# Power_switch_robot_kecil.net
KiCad netlist of a schematic drawn in EAGLE
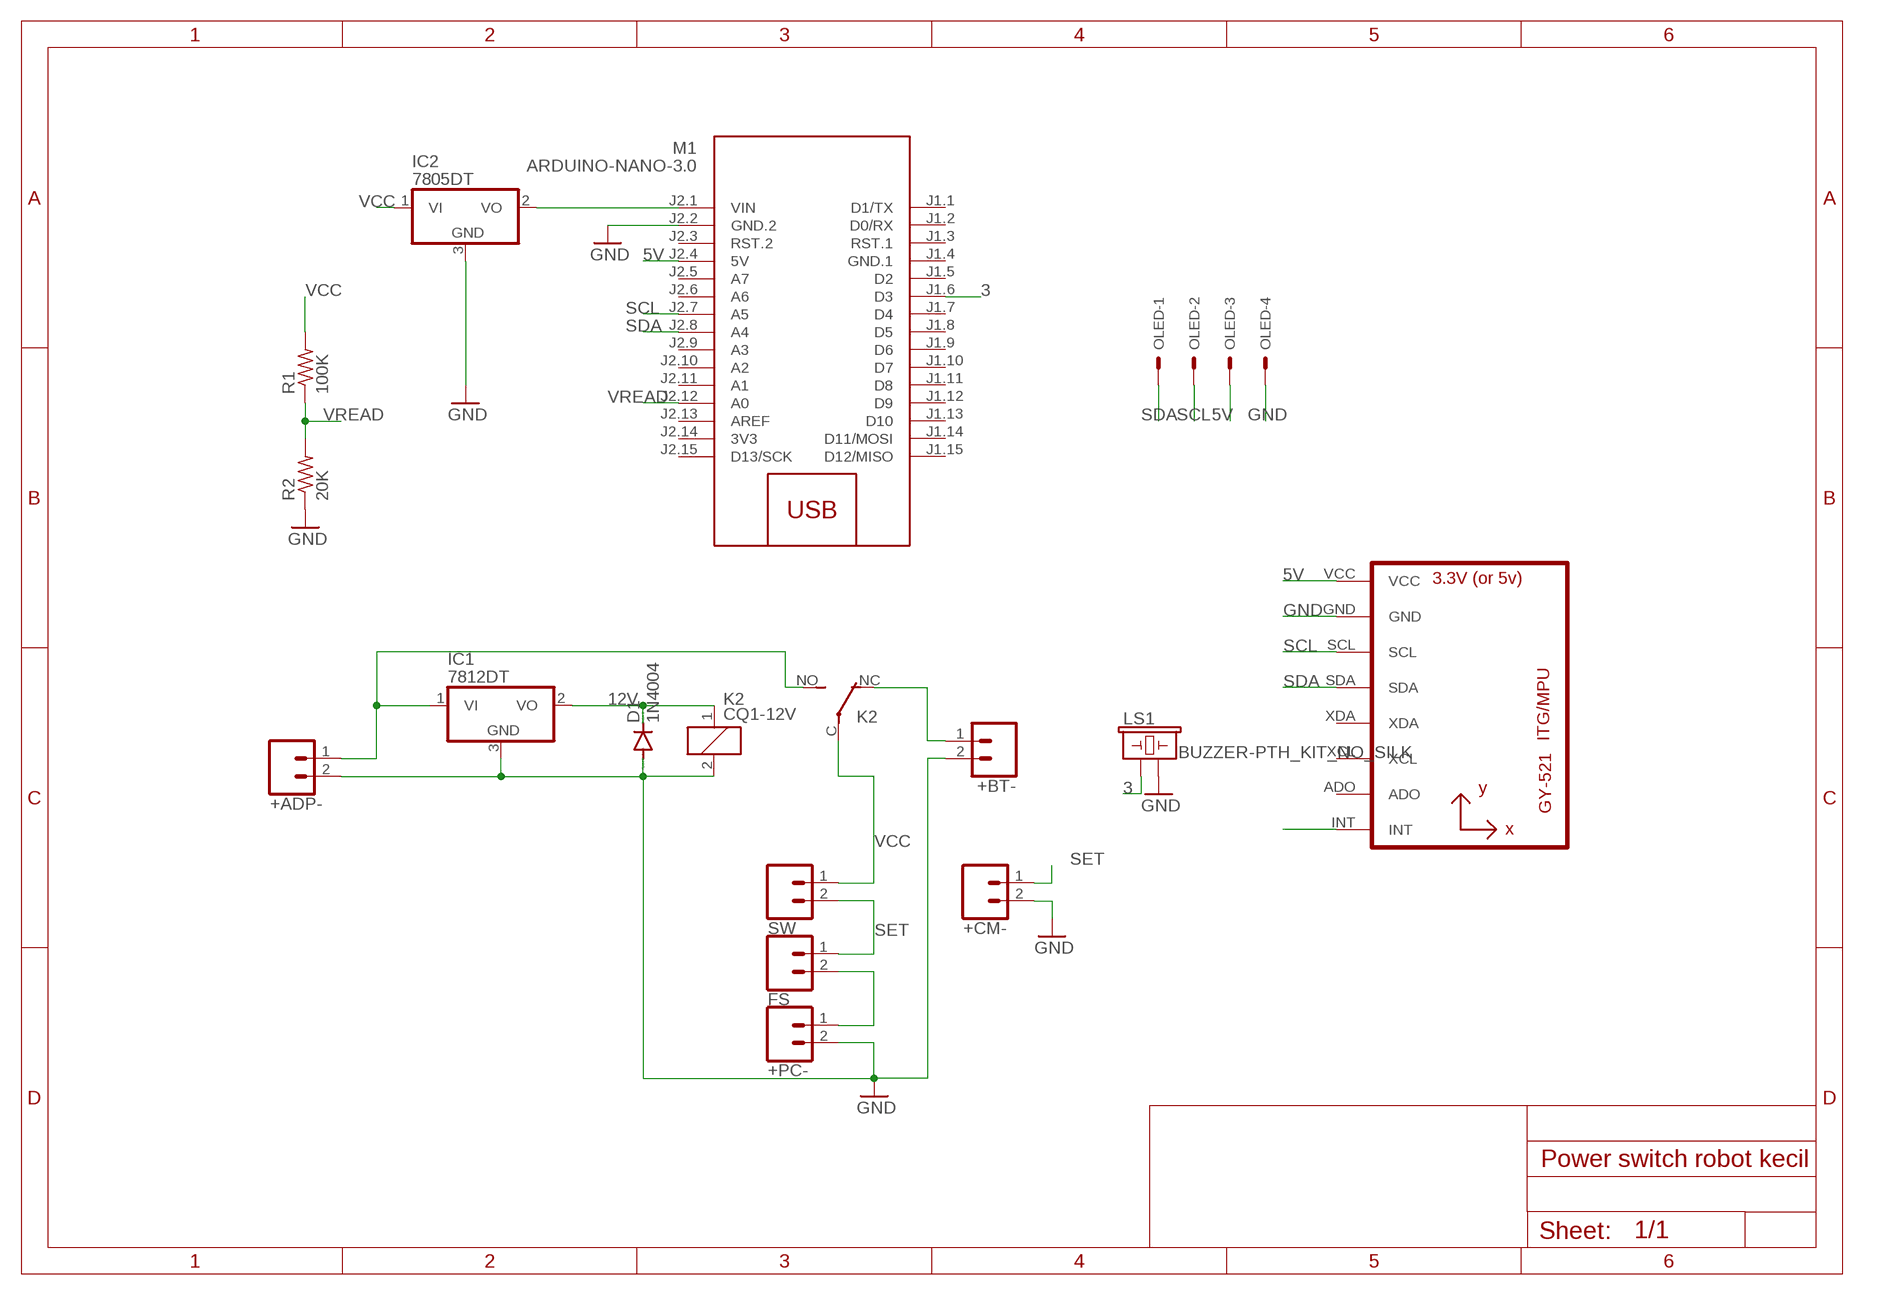
[diagram p0: schematic, sheet 1]

(export (version "E")
  (design (tool "Eeschema 10.0.6"))
  (components
    (comp (ref "+ADP-")
      (value "CONN_02PTH4")
      (footprint "eagle-import:1X02_XTRA_BIG")
      (libsource (lib "eagle-import") (part "CONN_02PTH4"))
    )
    (comp (ref "+BT-")
      (value "CONN_02PTH4")
      (footprint "eagle-import:1X02_XTRA_BIG")
      (libsource (lib "eagle-import") (part "CONN_02PTH4"))
    )
    (comp (ref "+CM-")
      (value "CONN_02PTH4")
      (footprint "eagle-import:1X02_XTRA_BIG")
      (libsource (lib "eagle-import") (part "CONN_02PTH4"))
    )
    (comp (ref "+PC-")
      (value "CONN_02PTH4")
      (footprint "eagle-import:1X02_XTRA_BIG")
      (libsource (lib "eagle-import") (part "CONN_02PTH4"))
    )
    (comp (ref "D1")
      (value "1N4004")
      (footprint "eagle-import:DO41-10")
      (libsource (lib "eagle-import") (part "1N4004"))
    )
    (comp (ref "FS")
      (value "CONN_02PTH4")
      (footprint "eagle-import:1X02_XTRA_BIG")
      (libsource (lib "eagle-import") (part "CONN_02PTH4"))
    )
    (comp (ref "IC1")
      (value "7812DT")
      (footprint "eagle-import:TO252")
      (libsource (lib "eagle-import") (part "78DT12"))
    )
    (comp (ref "IC2")
      (value "7805DT")
      (footprint "eagle-import:TO252")
      (libsource (lib "eagle-import") (part "78DT05"))
    )
    (comp (ref "K2")
      (value "CQ1-12V")
      (footprint "eagle-import:CQ1")
      (libsource (lib "eagle-import") (part "CQ1-12V"))
    )
    (comp (ref "LS1")
      (value "BUZZER-PTH_KIT_NO_SILK")
      (footprint "eagle-import:BUZZER-12MM-NS-KIT")
      (libsource (lib "eagle-import") (part "BUZZER-PTH_KIT_NO_SILK"))
    )
    (comp (ref "M1")
      (value "ARDUINO-NANO-3.0")
      (footprint "eagle-import:ARDUINO-NANO-3.0")
      (libsource (lib "eagle-import") (part "ARDUINO-NANO-3.0"))
    )
    (comp (ref "OLED")
      (value "22-27-2041-04")
      (footprint "eagle-import:6410-04")
      (fields (field (name "MF") "MOLEX"))
      (libsource (lib "eagle-import") (part "22-?-0427-2041"))
    )
    (comp (ref "R1")
      (value "100K")
      (footprint "eagle-import:0207_10")
      (libsource (lib "eagle-import") (part "R-US_0207/10"))
    )
    (comp (ref "R2")
      (value "20K")
      (footprint "eagle-import:0207_10")
      (libsource (lib "eagle-import") (part "R-US_0207/10"))
    )
    (comp (ref "SW")
      (value "CONN_02PTH4")
      (footprint "eagle-import:1X02_XTRA_BIG")
      (libsource (lib "eagle-import") (part "CONN_02PTH4"))
    )
    (comp (ref "U1")
      (value "GY-521MPU6050")
      (footprint "eagle-import:GY-521")
      (libsource (lib "eagle-import") (part "GY-521MPU6050"))
    )
  )
  (nets
    (net (code "1") (name "/3") (class "Default")
      (node (ref "LS1") (pin "+") (pinfunction "1_+") (pintype "passive"))
      (node (ref "M1") (pin "J1.6") (pinfunction "D3_J1.6") (pintype "bidirectional"))
    )
    (net (code "2") (name "/3V3") (class "Default")
      (node (ref "M1") (pin "J2.14") (pinfunction "3V3_J2.14") (pintype "power_in"))
    )
    (net (code "3") (name "/5V") (class "Default")
      (node (ref "M1") (pin "J2.4") (pinfunction "5V_J2.4") (pintype "power_in"))
      (node (ref "OLED") (pin "3") (pinfunction "S_3") (pintype "passive"))
      (node (ref "U1") (pin "VCC") (pinfunction "VCC_VCC") (pintype "bidirectional"))
    )
    (net (code "4") (name "/12V") (class "Default")
      (node (ref "D1") (pin "C") (pinfunction "C_C") (pintype "passive"))
      (node (ref "IC1") (pin "2") (pinfunction "VO_2") (pintype "passive"))
      (node (ref "K2") (pin "1") (pinfunction "1_1") (pintype "passive"))
    )
    (net (code "5") (name "/GND.1") (class "Default")
      (node (ref "M1") (pin "J1.4") (pinfunction "GND.1_J1.4") (pintype "power_in"))
    )
    (net (code "6") (name "/SCL") (class "Default")
      (node (ref "M1") (pin "J2.7") (pinfunction "A5_J2.7") (pintype "bidirectional"))
      (node (ref "OLED") (pin "2") (pinfunction "S_2") (pintype "passive"))
      (node (ref "U1") (pin "SCL") (pinfunction "SCL_SCL") (pintype "bidirectional"))
    )
    (net (code "7") (name "/SDA") (class "Default")
      (node (ref "M1") (pin "J2.8") (pinfunction "A4_J2.8") (pintype "bidirectional"))
      (node (ref "OLED") (pin "1") (pinfunction "S_1") (pintype "passive"))
      (node (ref "U1") (pin "SDA") (pinfunction "SDA_SDA") (pintype "bidirectional"))
    )
    (net (code "8") (name "/SET") (class "Default")
      (node (ref "+CM-") (pin "1") (pinfunction "1_1") (pintype "passive"))
      (node (ref "FS") (pin "1") (pinfunction "1_1") (pintype "passive"))
      (node (ref "SW") (pin "2") (pinfunction "2_2") (pintype "passive"))
    )
    (net (code "9") (name "/VCC") (class "Default")
      (node (ref "IC2") (pin "1") (pinfunction "VI_1") (pintype "input"))
      (node (ref "K2") (pin "C") (pinfunction "P_C") (pintype "passive"))
      (node (ref "R1") (pin "2") (pinfunction "2_2") (pintype "passive"))
      (node (ref "SW") (pin "1") (pinfunction "1_1") (pintype "passive"))
    )
    (net (code "10") (name "/VREAD") (class "Default")
      (node (ref "M1") (pin "J2.12") (pinfunction "A0_J2.12") (pintype "bidirectional"))
      (node (ref "R1") (pin "1") (pinfunction "1_1") (pintype "passive"))
      (node (ref "R2") (pin "2") (pinfunction "2_2") (pintype "passive"))
    )
    (net (code "11") (name "GND") (class "Default")
      (node (ref "+ADP-") (pin "2") (pinfunction "2_2") (pintype "passive"))
      (node (ref "+BT-") (pin "2") (pinfunction "2_2") (pintype "passive"))
      (node (ref "+CM-") (pin "2") (pinfunction "2_2") (pintype "passive"))
      (node (ref "+PC-") (pin "2") (pinfunction "2_2") (pintype "passive"))
      (node (ref "D1") (pin "A") (pinfunction "A_A") (pintype "passive"))
      (node (ref "IC1") (pin "3") (pinfunction "GND_3") (pintype "passive"))
      (node (ref "IC2") (pin "3") (pinfunction "GND_3") (pintype "passive"))
      (node (ref "K2") (pin "2") (pinfunction "2_2") (pintype "passive"))
      (node (ref "LS1") (pin "-") (pinfunction "2_-") (pintype "passive"))
      (node (ref "M1") (pin "J2.2") (pinfunction "GND.2_J2.2") (pintype "power_in"))
      (node (ref "OLED") (pin "4") (pinfunction "S_4") (pintype "passive"))
      (node (ref "R2") (pin "1") (pinfunction "1_1") (pintype "passive"))
      (node (ref "U1") (pin "GND") (pinfunction "GND_GND") (pintype "bidirectional"))
    )
    (net (code "12") (name "Net-(+PC--Pad1)") (class "Default")
      (node (ref "+PC-") (pin "1") (pinfunction "1_1") (pintype "passive"))
      (node (ref "FS") (pin "2") (pinfunction "2_2") (pintype "passive"))
    )
    (net (code "13") (name "Net-(IC1-VI)") (class "Default")
      (node (ref "+ADP-") (pin "1") (pinfunction "1_1") (pintype "passive"))
      (node (ref "IC1") (pin "1") (pinfunction "VI_1") (pintype "input"))
      (node (ref "K2") (pin "NO") (pinfunction "S_NO") (pintype "passive"))
    )
    (net (code "14") (name "Net-(IC2-VO)") (class "Default")
      (node (ref "IC2") (pin "2") (pinfunction "VO_2") (pintype "passive"))
      (node (ref "M1") (pin "J2.1") (pinfunction "VIN_J2.1") (pintype "power_in"))
    )
    (net (code "15") (name "Net-(K2B-O)") (class "Default")
      (node (ref "+BT-") (pin "1") (pinfunction "1_1") (pintype "passive"))
      (node (ref "K2") (pin "NC") (pinfunction "O_NC") (pintype "passive"))
    )
    (net (code "16") (name "unconnected-(M1-A1-PadJ2.11)") (class "Default")
      (node (ref "M1") (pin "J2.11") (pinfunction "A1_J2.11") (pintype "bidirectional"))
    )
    (net (code "17") (name "unconnected-(M1-A2-PadJ2.10)") (class "Default")
      (node (ref "M1") (pin "J2.10") (pinfunction "A2_J2.10") (pintype "bidirectional"))
    )
    (net (code "18") (name "unconnected-(M1-A3-PadJ2.9)") (class "Default")
      (node (ref "M1") (pin "J2.9") (pinfunction "A3_J2.9") (pintype "bidirectional"))
    )
    (net (code "19") (name "unconnected-(M1-A6-PadJ2.6)") (class "Default")
      (node (ref "M1") (pin "J2.6") (pinfunction "A6_J2.6") (pintype "bidirectional"))
    )
    (net (code "20") (name "unconnected-(M1-A7-PadJ2.5)") (class "Default")
      (node (ref "M1") (pin "J2.5") (pinfunction "A7_J2.5") (pintype "bidirectional"))
    )
    (net (code "21") (name "unconnected-(M1-AREF-PadJ2.13)") (class "Default")
      (node (ref "M1") (pin "J2.13") (pinfunction "AREF_J2.13") (pintype "bidirectional"))
    )
    (net (code "22") (name "unconnected-(M1-D0{slash}RX-PadJ1.2)") (class "Default")
      (node (ref "M1") (pin "J1.2") (pinfunction "D0/RX_J1.2") (pintype "bidirectional"))
    )
    (net (code "23") (name "unconnected-(M1-D1{slash}TX-PadJ1.1)") (class "Default")
      (node (ref "M1") (pin "J1.1") (pinfunction "D1/TX_J1.1") (pintype "bidirectional"))
    )
    (net (code "24") (name "unconnected-(M1-D2-PadJ1.5)") (class "Default")
      (node (ref "M1") (pin "J1.5") (pinfunction "D2_J1.5") (pintype "bidirectional"))
    )
    (net (code "25") (name "unconnected-(M1-D4-PadJ1.7)") (class "Default")
      (node (ref "M1") (pin "J1.7") (pinfunction "D4_J1.7") (pintype "bidirectional"))
    )
    (net (code "26") (name "unconnected-(M1-D5-PadJ1.8)") (class "Default")
      (node (ref "M1") (pin "J1.8") (pinfunction "D5_J1.8") (pintype "bidirectional"))
    )
    (net (code "27") (name "unconnected-(M1-D6-PadJ1.9)") (class "Default")
      (node (ref "M1") (pin "J1.9") (pinfunction "D6_J1.9") (pintype "bidirectional"))
    )
    (net (code "28") (name "unconnected-(M1-D7-PadJ1.10)") (class "Default")
      (node (ref "M1") (pin "J1.10") (pinfunction "D7_J1.10") (pintype "bidirectional"))
    )
    (net (code "29") (name "unconnected-(M1-D8-PadJ1.11)") (class "Default")
      (node (ref "M1") (pin "J1.11") (pinfunction "D8_J1.11") (pintype "bidirectional"))
    )
    (net (code "30") (name "unconnected-(M1-D9-PadJ1.12)") (class "Default")
      (node (ref "M1") (pin "J1.12") (pinfunction "D9_J1.12") (pintype "bidirectional"))
    )
    (net (code "31") (name "unconnected-(M1-D10-PadJ1.13)") (class "Default")
      (node (ref "M1") (pin "J1.13") (pinfunction "D10_J1.13") (pintype "bidirectional"))
    )
    (net (code "32") (name "unconnected-(M1-D11{slash}MOSI-PadJ1.14)") (class "Default")
      (node (ref "M1") (pin "J1.14") (pinfunction "D11/MOSI_J1.14") (pintype "bidirectional"))
    )
    (net (code "33") (name "unconnected-(M1-D12{slash}MISO-PadJ1.15)") (class "Default")
      (node (ref "M1") (pin "J1.15") (pinfunction "D12/MISO_J1.15") (pintype "bidirectional"))
    )
    (net (code "34") (name "unconnected-(M1-D13{slash}SCK-PadJ2.15)") (class "Default")
      (node (ref "M1") (pin "J2.15") (pinfunction "D13/SCK_J2.15") (pintype "bidirectional"))
    )
    (net (code "35") (name "unconnected-(M1-RST.1-PadJ1.3)") (class "Default")
      (node (ref "M1") (pin "J1.3") (pinfunction "RST.1_J1.3") (pintype "bidirectional"))
    )
    (net (code "36") (name "unconnected-(M1-RST.2-PadJ2.3)") (class "Default")
      (node (ref "M1") (pin "J2.3") (pinfunction "RST.2_J2.3") (pintype "bidirectional"))
    )
    (net (code "37") (name "unconnected-(U1-PadADO)") (class "Default")
      (node (ref "U1") (pin "ADO") (pinfunction "ADO_ADO") (pintype "bidirectional"))
    )
    (net (code "38") (name "unconnected-(U1-PadINT)") (class "Default")
      (node (ref "U1") (pin "INT") (pinfunction "INT_INT") (pintype "bidirectional"))
    )
    (net (code "39") (name "unconnected-(U1-PadXCL)") (class "Default")
      (node (ref "U1") (pin "XCL") (pinfunction "XCL_XCL") (pintype "bidirectional"))
    )
    (net (code "40") (name "unconnected-(U1-PadXDA)") (class "Default")
      (node (ref "U1") (pin "XDA") (pinfunction "XDA_XDA") (pintype "bidirectional"))
    )
  )
)
